# rhiozme_2_0_pid_interface_w_term.net
KiCad netlist of a schematic drawn in EAGLE
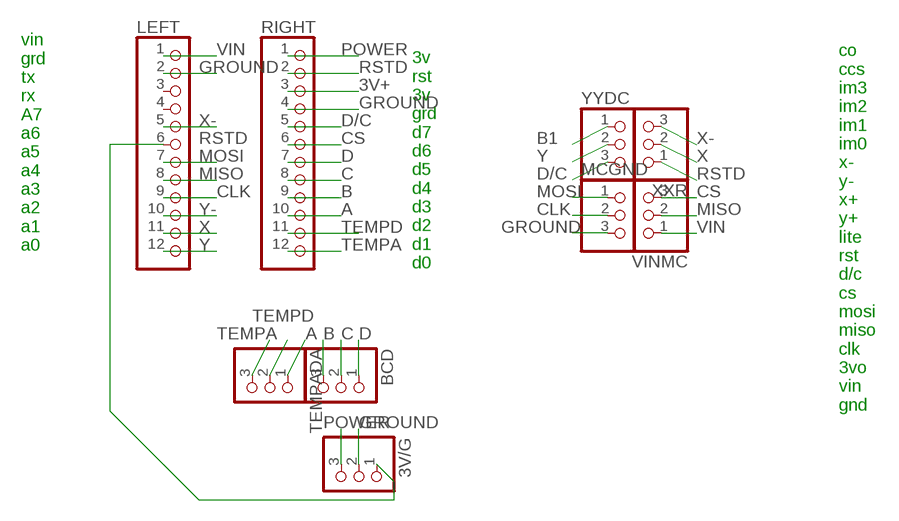
[diagram p0: schematic, sheet 1]

(export (version "E")
  (design (tool "Eeschema 10.0.6"))
  (components
    (comp (ref "3V/G")
      (value "PINHD-1X3CB")
      (footprint "eagle-import:1X03-CLEANBIG")
      (libsource (lib "eagle-import") (part "PINHD-1X3CB"))
    )
    (comp (ref "BCD")
      (value "PINHD-1X3CB")
      (footprint "eagle-import:1X03-CLEANBIG")
      (libsource (lib "eagle-import") (part "PINHD-1X3CB"))
    )
    (comp (ref "LEFT")
      (value "PINHD-1X12-CB")
      (footprint "eagle-import:1X12-CB")
      (libsource (lib "eagle-import") (part "PINHD-1X12-CB"))
    )
    (comp (ref "MCGND")
      (value "PINHD-1X3CB")
      (footprint "eagle-import:1X03-CLEANBIG")
      (libsource (lib "eagle-import") (part "PINHD-1X3CB"))
    )
    (comp (ref "RIGHT")
      (value "PINHD-1X12-CB")
      (footprint "eagle-import:1X12-CB")
      (libsource (lib "eagle-import") (part "PINHD-1X12-CB"))
    )
    (comp (ref "TEMPADA")
      (value "PINHD-1X3CB")
      (footprint "eagle-import:1X03-CLEANBIG")
      (libsource (lib "eagle-import") (part "PINHD-1X3CB"))
    )
    (comp (ref "VINMC")
      (value "PINHD-1X3CB")
      (footprint "eagle-import:1X03-CLEANBIG")
      (libsource (lib "eagle-import") (part "PINHD-1X3CB"))
    )
    (comp (ref "XXR")
      (value "PINHD-1X3CB")
      (footprint "eagle-import:1X03-CLEANBIG")
      (libsource (lib "eagle-import") (part "PINHD-1X3CB"))
    )
    (comp (ref "YYDC")
      (value "PINHD-1X3CB")
      (footprint "eagle-import:1X03-CLEANBIG")
      (libsource (lib "eagle-import") (part "PINHD-1X3CB"))
    )
  )
  (nets
    (net (code "1") (name "/3V+") (class "Default")
      (node (ref "RIGHT") (pin "3") (pinfunction "3_3") (pintype "passive"))
    )
    (net (code "2") (name "/A") (class "Default")
      (node (ref "RIGHT") (pin "10") (pinfunction "10_10") (pintype "passive"))
      (node (ref "TEMPADA") (pin "1") (pinfunction "1_1") (pintype "passive"))
    )
    (net (code "3") (name "/B") (class "Default")
      (node (ref "BCD") (pin "3") (pinfunction "3_3") (pintype "passive"))
      (node (ref "RIGHT") (pin "9") (pinfunction "9_9") (pintype "passive"))
    )
    (net (code "4") (name "/B1") (class "Default")
      (node (ref "YYDC") (pin "1") (pinfunction "1_1") (pintype "passive"))
    )
    (net (code "5") (name "/C") (class "Default")
      (node (ref "BCD") (pin "2") (pinfunction "2_2") (pintype "passive"))
      (node (ref "RIGHT") (pin "8") (pinfunction "8_8") (pintype "passive"))
    )
    (net (code "6") (name "/CLK") (class "Default")
      (node (ref "LEFT") (pin "9") (pinfunction "9_9") (pintype "passive"))
      (node (ref "MCGND") (pin "2") (pinfunction "2_2") (pintype "passive"))
    )
    (net (code "7") (name "/CS") (class "Default")
      (node (ref "RIGHT") (pin "6") (pinfunction "6_6") (pintype "passive"))
      (node (ref "VINMC") (pin "3") (pinfunction "3_3") (pintype "passive"))
    )
    (net (code "8") (name "/D") (class "Default")
      (node (ref "BCD") (pin "1") (pinfunction "1_1") (pintype "passive"))
      (node (ref "RIGHT") (pin "7") (pinfunction "7_7") (pintype "passive"))
    )
    (net (code "9") (name "/D{slash}C") (class "Default")
      (node (ref "RIGHT") (pin "5") (pinfunction "5_5") (pintype "passive"))
      (node (ref "YYDC") (pin "3") (pinfunction "3_3") (pintype "passive"))
    )
    (net (code "10") (name "/GROUND") (class "Default")
      (node (ref "3V/G") (pin "2") (pinfunction "2_2") (pintype "passive"))
      (node (ref "LEFT") (pin "2") (pinfunction "2_2") (pintype "passive"))
      (node (ref "MCGND") (pin "3") (pinfunction "3_3") (pintype "passive"))
      (node (ref "RIGHT") (pin "4") (pinfunction "4_4") (pintype "passive"))
    )
    (net (code "11") (name "/MISO") (class "Default")
      (node (ref "LEFT") (pin "8") (pinfunction "8_8") (pintype "passive"))
      (node (ref "VINMC") (pin "2") (pinfunction "2_2") (pintype "passive"))
    )
    (net (code "12") (name "/MOSI") (class "Default")
      (node (ref "LEFT") (pin "7") (pinfunction "7_7") (pintype "passive"))
      (node (ref "MCGND") (pin "1") (pinfunction "1_1") (pintype "passive"))
    )
    (net (code "13") (name "/POWER") (class "Default")
      (node (ref "3V/G") (pin "3") (pinfunction "3_3") (pintype "passive"))
      (node (ref "RIGHT") (pin "1") (pinfunction "1_1") (pintype "passive"))
    )
    (net (code "14") (name "/RSTD") (class "Default")
      (node (ref "RIGHT") (pin "2") (pinfunction "2_2") (pintype "passive"))
      (node (ref "XXR") (pin "1") (pinfunction "1_1") (pintype "passive"))
    )
    (net (code "15") (name "/TEMPA") (class "Default")
      (node (ref "RIGHT") (pin "12") (pinfunction "12_12") (pintype "passive"))
      (node (ref "TEMPADA") (pin "3") (pinfunction "3_3") (pintype "passive"))
    )
    (net (code "16") (name "/TEMPD") (class "Default")
      (node (ref "RIGHT") (pin "11") (pinfunction "11_11") (pintype "passive"))
      (node (ref "TEMPADA") (pin "2") (pinfunction "2_2") (pintype "passive"))
    )
    (net (code "17") (name "/VIN") (class "Default")
      (node (ref "LEFT") (pin "1") (pinfunction "1_1") (pintype "passive"))
      (node (ref "VINMC") (pin "1") (pinfunction "1_1") (pintype "passive"))
    )
    (net (code "18") (name "/X") (class "Default")
      (node (ref "LEFT") (pin "11") (pinfunction "11_11") (pintype "passive"))
      (node (ref "XXR") (pin "2") (pinfunction "2_2") (pintype "passive"))
    )
    (net (code "19") (name "/X-") (class "Default")
      (node (ref "LEFT") (pin "5") (pinfunction "5_5") (pintype "passive"))
      (node (ref "XXR") (pin "3") (pinfunction "3_3") (pintype "passive"))
    )
    (net (code "20") (name "/Y") (class "Default")
      (node (ref "LEFT") (pin "12") (pinfunction "12_12") (pintype "passive"))
      (node (ref "YYDC") (pin "2") (pinfunction "2_2") (pintype "passive"))
    )
    (net (code "21") (name "/Y-") (class "Default")
      (node (ref "LEFT") (pin "10") (pinfunction "10_10") (pintype "passive"))
    )
    (net (code "22") (name "Net-(3V/G-Pad1)") (class "Default")
      (node (ref "3V/G") (pin "1") (pinfunction "1_1") (pintype "passive"))
      (node (ref "LEFT") (pin "6") (pinfunction "6_6") (pintype "passive"))
    )
    (net (code "23") (name "unconnected-(LEFT-Pad3)") (class "Default")
      (node (ref "LEFT") (pin "3") (pinfunction "3_3") (pintype "passive"))
    )
    (net (code "24") (name "unconnected-(LEFT-Pad4)") (class "Default")
      (node (ref "LEFT") (pin "4") (pinfunction "4_4") (pintype "passive"))
    )
  )
)
